# MED_ESP32_C3_0002.net
KiCad netlist of a schematic drawn in EAGLE
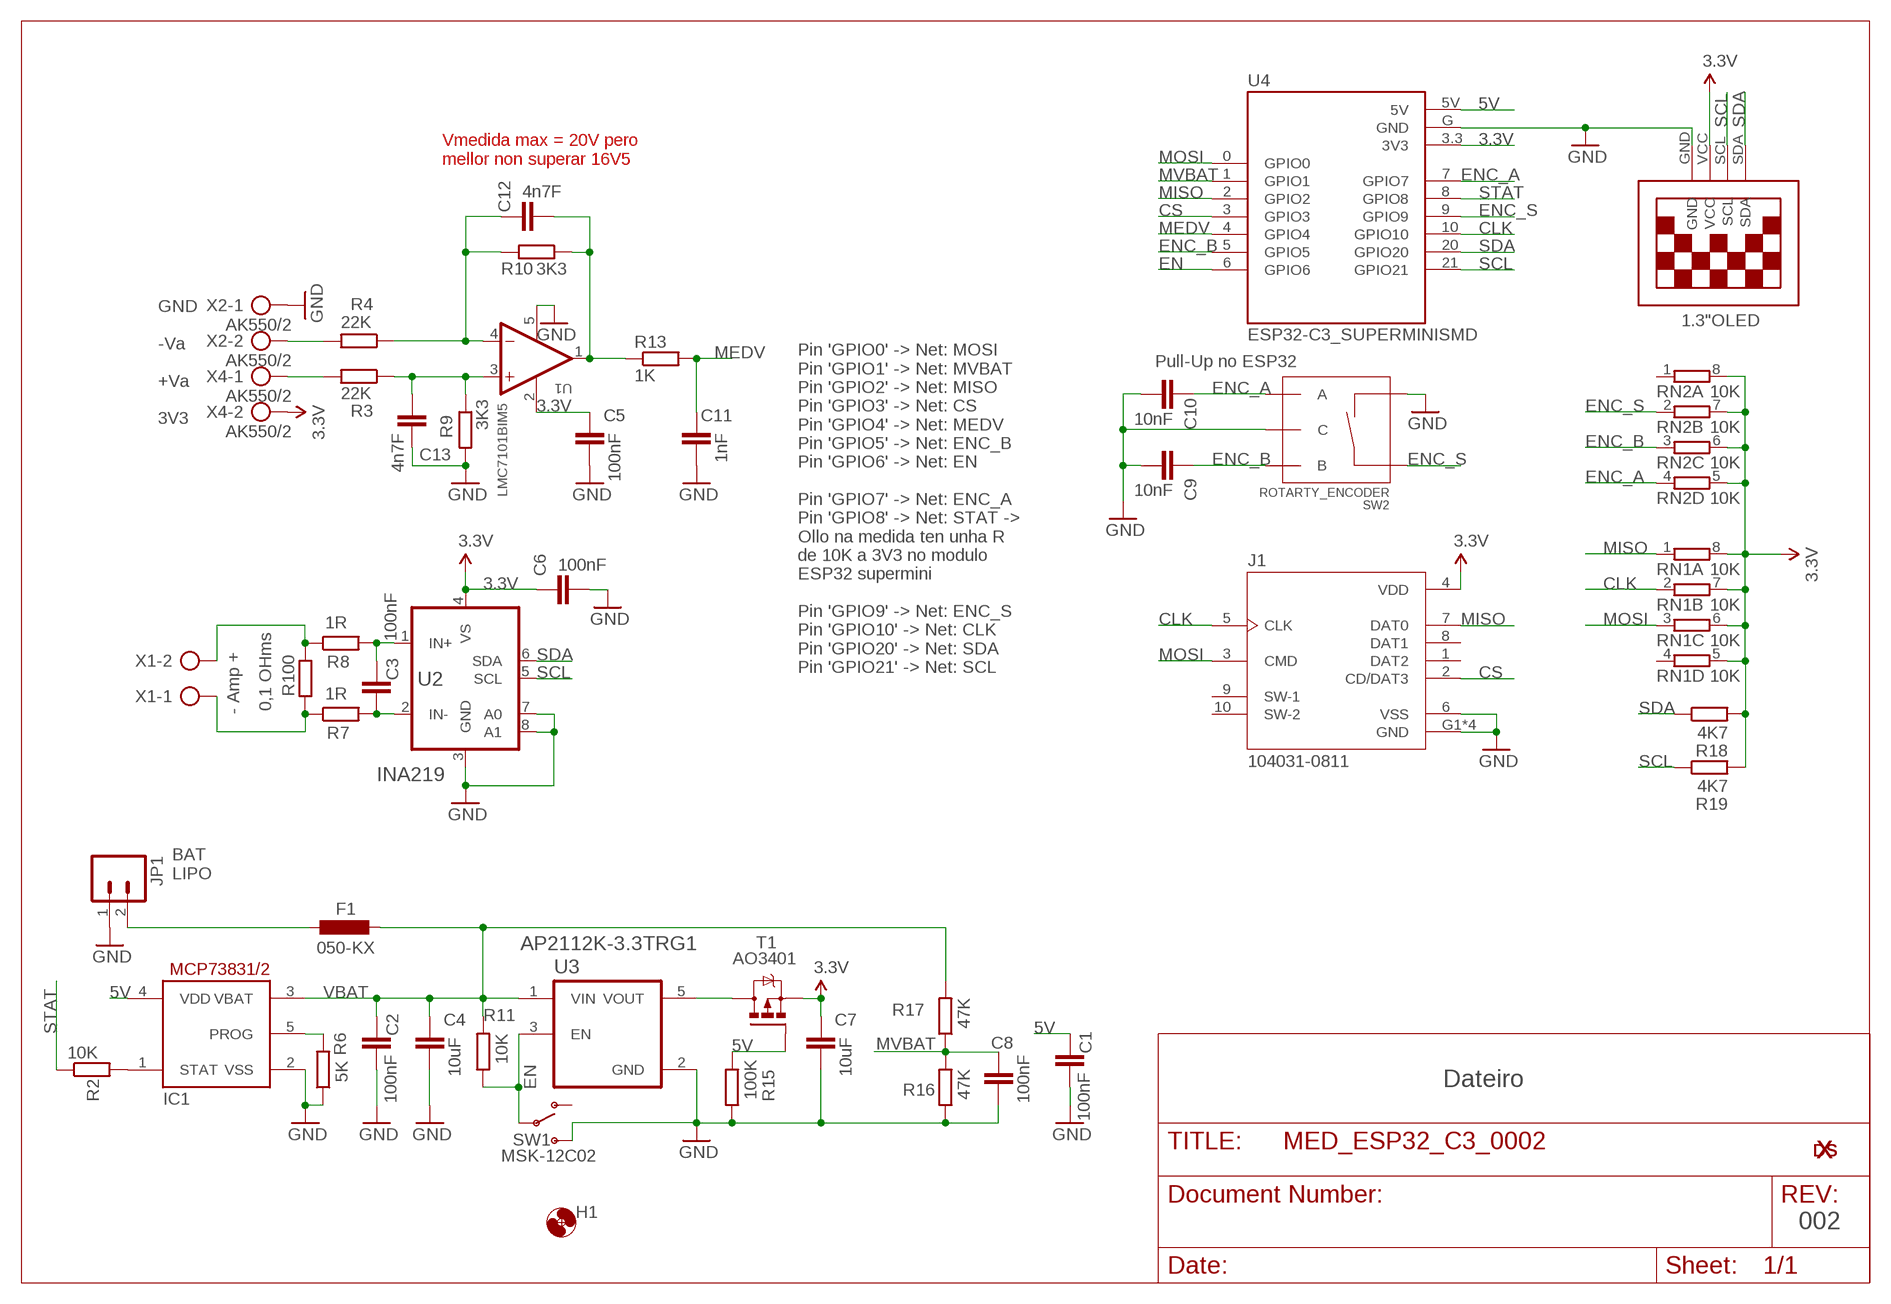
[diagram p0: schematic, sheet 1]

(export (version "E")
  (design (tool "Eeschema 10.0.6"))
  (components
    (comp (ref "C1")
      (value "100nF")
      (footprint "eagle-import:C0603")
      (libsource (lib "eagle-import") (part "C-EUC0603"))
    )
    (comp (ref "C2")
      (value "100nF")
      (footprint "eagle-import:C0603")
      (libsource (lib "eagle-import") (part "C-EUC0603"))
    )
    (comp (ref "C3")
      (value "100nF")
      (footprint "eagle-import:C0603")
      (libsource (lib "eagle-import") (part "C-EUC0603"))
    )
    (comp (ref "C4")
      (value "10uF")
      (footprint "eagle-import:C1206")
      (libsource (lib "eagle-import") (part "C-EUC1206"))
    )
    (comp (ref "C5")
      (value "100nF")
      (footprint "eagle-import:C0603")
      (libsource (lib "eagle-import") (part "C-EUC0603"))
    )
    (comp (ref "C6")
      (value "100nF")
      (footprint "eagle-import:C0603")
      (libsource (lib "eagle-import") (part "C-EUC0603"))
    )
    (comp (ref "C7")
      (value "10uF")
      (footprint "eagle-import:C1206")
      (libsource (lib "eagle-import") (part "C-EUC1206"))
    )
    (comp (ref "C8")
      (value "100nF")
      (footprint "eagle-import:C0603")
      (libsource (lib "eagle-import") (part "C-EUC0603"))
    )
    (comp (ref "C9")
      (value "10nF")
      (footprint "eagle-import:C0603")
      (libsource (lib "eagle-import") (part "C-EUC0603"))
    )
    (comp (ref "C10")
      (value "10nF")
      (footprint "eagle-import:C0603")
      (libsource (lib "eagle-import") (part "C-EUC0603"))
    )
    (comp (ref "C11")
      (value "1nF")
      (footprint "eagle-import:C0603")
      (libsource (lib "eagle-import") (part "C-EUC0603"))
    )
    (comp (ref "C12")
      (value "4n7F")
      (footprint "eagle-import:C0603")
      (libsource (lib "eagle-import") (part "C-EUC0603"))
    )
    (comp (ref "C13")
      (value "4n7F")
      (footprint "eagle-import:C0603")
      (libsource (lib "eagle-import") (part "C-EUC0603"))
    )
    (comp (ref "F1")
      (value "050-KX")
      (footprint "eagle-import:L3225M")
      (libsource (lib "eagle-import") (part "L-EUL3225M"))
    )
    (comp (ref "H1")
      (value "HOLES_MOUNT-HOLE3.2")
      (footprint "eagle-import:HOLES_3,2")
      (libsource (lib "eagle-import") (part "HOLES_MOUNT-HOLE3.2"))
    )
    (comp (ref "IC1")
      (value "MCP73831T-2")
      (footprint "eagle-import:SOT23-5L")
      (libsource (lib "eagle-import") (part "MCP73831/OT"))
    )
    (comp (ref "J1")
      (value "104031-0811")
      (footprint "eagle-import:MOLEX_104031-0811")
      (fields (field (name "MF") "Molex"))
      (libsource (lib "eagle-import") (part "104031-0811"))
    )
    (comp (ref "JP1")
      (value "M02JST-PTH-VERT")
      (footprint "eagle-import:JST-2-PTH-VERT")
      (libsource (lib "eagle-import") (part "M02JST-PTH-VERT"))
    )
    (comp (ref "R2")
      (value "10K")
      (footprint "eagle-import:R0603")
      (libsource (lib "eagle-import") (part "R-EU_R0603"))
    )
    (comp (ref "R3")
      (value "22K")
      (footprint "eagle-import:R0603")
      (libsource (lib "eagle-import") (part "R-EU_R0603"))
    )
    (comp (ref "R4")
      (value "22K")
      (footprint "eagle-import:R0603")
      (libsource (lib "eagle-import") (part "R-EU_R0603"))
    )
    (comp (ref "R5")
      (value "R100")
      (footprint "eagle-import:R1210")
      (libsource (lib "eagle-import") (part "R-EU_R1210"))
    )
    (comp (ref "R6")
      (value "5K")
      (footprint "eagle-import:R0603")
      (libsource (lib "eagle-import") (part "R-EU_R0603"))
    )
    (comp (ref "R7")
      (value "1R")
      (footprint "eagle-import:R0603")
      (libsource (lib "eagle-import") (part "R-EU_R0603"))
    )
    (comp (ref "R8")
      (value "1R")
      (footprint "eagle-import:R0603")
      (libsource (lib "eagle-import") (part "R-EU_R0603"))
    )
    (comp (ref "R9")
      (value "3K3")
      (footprint "eagle-import:R0603")
      (libsource (lib "eagle-import") (part "R-EU_R0603"))
    )
    (comp (ref "R10")
      (value "3K3")
      (footprint "eagle-import:R0603")
      (libsource (lib "eagle-import") (part "R-EU_R0603"))
    )
    (comp (ref "R11")
      (value "10K")
      (footprint "eagle-import:R0603")
      (libsource (lib "eagle-import") (part "R-EU_R0603"))
    )
    (comp (ref "R13")
      (value "1K")
      (footprint "eagle-import:R0603")
      (libsource (lib "eagle-import") (part "R-EU_R0603"))
    )
    (comp (ref "R15")
      (value "100K")
      (footprint "eagle-import:R0603")
      (libsource (lib "eagle-import") (part "R-EU_R0603"))
    )
    (comp (ref "R16")
      (value "47K")
      (footprint "eagle-import:R0603")
      (libsource (lib "eagle-import") (part "R-EU_R0603"))
    )
    (comp (ref "R17")
      (value "47K")
      (footprint "eagle-import:R0603")
      (libsource (lib "eagle-import") (part "R-EU_R0603"))
    )
    (comp (ref "R18")
      (value "4K7")
      (footprint "eagle-import:R0603")
      (libsource (lib "eagle-import") (part "R-EU_R0603"))
    )
    (comp (ref "R19")
      (value "4K7")
      (footprint "eagle-import:R0603")
      (libsource (lib "eagle-import") (part "R-EU_R0603"))
    )
    (comp (ref "RN1")
      (value "10K")
      (footprint "eagle-import:RESISTOR-DIL_0603-ARC")
      (libsource (lib "eagle-import") (part "RESISTOR-DIL_4R-N0603-ARC"))
    )
    (comp (ref "RN2")
      (value "10K")
      (footprint "eagle-import:RESISTOR-DIL_0603-ARV")
      (libsource (lib "eagle-import") (part "RESISTOR-DIL_4R-N0603-ARV"))
    )
    (comp (ref "SW1")
      (value "MSK-12C02")
      (footprint "eagle-import:KPS-1290")
      (libsource (lib "eagle-import") (part "SWITCH_SPDT"))
    )
    (comp (ref "SW2")
      (value "ROTARTY_ENCODER")
      (footprint "eagle-import:ROTARY_ENC_PLAIN")
      (libsource (lib "eagle-import") (part "ROTARTY_ENCODER"))
    )
    (comp (ref "T1")
      (value "AO3401")
      (footprint "eagle-import:SOT23")
      (libsource (lib "eagle-import") (part "MOSFET-PCHANNEL"))
    )
    (comp (ref "U$1")
      (value "13\"OLED13\"OLED")
      (footprint "eagle-import:1.3_OLED")
      (libsource (lib "eagle-import") (part "13{dblquote}OLED13{dblquote}OLED"))
    )
    (comp (ref "U$2")
      (value "XDESIG5MM")
      (footprint "eagle-import:XDESIG_CU")
      (libsource (lib "eagle-import") (part "XDESIG5MM"))
    )
    (comp (ref "U$3")
      (value "XDESIG21")
      (footprint "eagle-import:XDESIG")
      (libsource (lib "eagle-import") (part "XDESIG21"))
    )
    (comp (ref "U$4")
      (value "XDESIG21")
      (footprint "eagle-import:XDESIG")
      (libsource (lib "eagle-import") (part "XDESIG21"))
    )
    (comp (ref "U$5")
      (value "XDESIG5MM")
      (footprint "eagle-import:XDESIG_CU")
      (libsource (lib "eagle-import") (part "XDESIG5MM"))
    )
    (comp (ref "U1")
      (value "LMC7101BIM5")
      (footprint "eagle-import:SOT95P280X145-5N")
      (fields (field (name "MF") "Texas Instruments") (field (name "MP") "LMC7101BIM5/NOPB"))
      (libsource (lib "eagle-import") (part "LMC7101BIM5"))
    )
    (comp (ref "U2")
      (value "INA219")
      (footprint "eagle-import:SOT65P280X145-8N")
      (fields (field (name "MF") "Texas Instruments") (field (name "MP") "INA219AIDCNRG4"))
      (libsource (lib "eagle-import") (part "INA219"))
    )
    (comp (ref "U3")
      (value "AP2112K-3.3TRG1")
      (footprint "eagle-import:SOT95P285X140-5N")
      (fields (field (name "MF") "Diodes Inc."))
      (libsource (lib "eagle-import") (part "AP2112K-3.3TRG1"))
    )
    (comp (ref "U4")
      (value "ESP32-C3_SUPERMINISMD")
      (footprint "eagle-import:MODULE_ESP-C3_SUPERMINI_SMD")
      (libsource (lib "eagle-import") (part "ESP32-C3_SUPERMINISMD"))
    )
    (comp (ref "X1")
      (value "AK500/2")
      (footprint "eagle-import:AK500_2")
      (libsource (lib "eagle-import") (part "AK500/2"))
    )
    (comp (ref "X2")
      (value "AK550/2")
      (footprint "eagle-import:AK550_2")
      (libsource (lib "eagle-import") (part "AK550/2"))
    )
    (comp (ref "X4")
      (value "AK550/2")
      (footprint "eagle-import:AK550_2")
      (libsource (lib "eagle-import") (part "AK550/2"))
    )
  )
  (nets
    (net (code "1") (name "/5V") (class "Default")
      (node (ref "C1") (pin "1") (pinfunction "1_1") (pintype "passive"))
      (node (ref "IC1") (pin "4") (pinfunction "VDD_4") (pintype "power_in"))
      (node (ref "R15") (pin "2") (pinfunction "2_2") (pintype "passive"))
      (node (ref "T1") (pin "1") (pinfunction "G_1") (pintype "passive"))
      (node (ref "U4") (pin "5V") (pinfunction "5V_5V") (pintype "power_in"))
    )
    (net (code "2") (name "/CLK") (class "Default")
      (node (ref "J1") (pin "5") (pinfunction "CLK_5") (pintype "input"))
      (node (ref "RN1") (pin "2") (pinfunction "1_2") (pintype "passive"))
      (node (ref "U4") (pin "10") (pinfunction "GPIO10_10") (pintype "bidirectional"))
    )
    (net (code "3") (name "/CS") (class "Default")
      (node (ref "J1") (pin "2") (pinfunction "CD/DAT3_2") (pintype "bidirectional"))
      (node (ref "U4") (pin "3") (pinfunction "GPIO3_3") (pintype "bidirectional"))
    )
    (net (code "4") (name "/EN") (class "Default")
      (node (ref "R11") (pin "1") (pinfunction "1_1") (pintype "passive"))
      (node (ref "SW1") (pin "P") (pinfunction "P_P") (pintype "passive"))
      (node (ref "U3") (pin "3") (pinfunction "EN_3") (pintype "input"))
      (node (ref "U4") (pin "6") (pinfunction "GPIO6_6") (pintype "bidirectional"))
    )
    (net (code "5") (name "/ENC_A") (class "Default")
      (node (ref "C10") (pin "2") (pinfunction "2_2") (pintype "passive"))
      (node (ref "RN2") (pin "4") (pinfunction "1_4") (pintype "passive"))
      (node (ref "SW2") (pin "A") (pinfunction "A_A") (pintype "bidirectional"))
      (node (ref "U4") (pin "7") (pinfunction "GPIO7_7") (pintype "bidirectional"))
    )
    (net (code "6") (name "/ENC_B") (class "Default")
      (node (ref "C9") (pin "2") (pinfunction "2_2") (pintype "passive"))
      (node (ref "RN2") (pin "3") (pinfunction "1_3") (pintype "passive"))
      (node (ref "SW2") (pin "B") (pinfunction "B_B") (pintype "bidirectional"))
      (node (ref "U4") (pin "5") (pinfunction "GPIO5_5") (pintype "bidirectional"))
    )
    (net (code "7") (name "/ENC_S") (class "Default")
      (node (ref "RN2") (pin "2") (pinfunction "1_2") (pintype "passive"))
      (node (ref "SW2") (pin "SW+") (pinfunction "SW+_SW+") (pintype "bidirectional"))
      (node (ref "U4") (pin "9") (pinfunction "GPIO9_9") (pintype "bidirectional"))
    )
    (net (code "8") (name "/MEDV") (class "Default")
      (node (ref "C11") (pin "2") (pinfunction "2_2") (pintype "passive"))
      (node (ref "R13") (pin "2") (pinfunction "2_2") (pintype "passive"))
      (node (ref "U4") (pin "4") (pinfunction "GPIO4_4") (pintype "bidirectional"))
    )
    (net (code "9") (name "/MISO") (class "Default")
      (node (ref "J1") (pin "7") (pinfunction "DAT0_7") (pintype "bidirectional"))
      (node (ref "RN1") (pin "1") (pinfunction "1_1") (pintype "passive"))
      (node (ref "U4") (pin "2") (pinfunction "GPIO2_2") (pintype "bidirectional"))
    )
    (net (code "10") (name "/MOSI") (class "Default")
      (node (ref "J1") (pin "3") (pinfunction "CMD_3") (pintype "bidirectional"))
      (node (ref "RN1") (pin "3") (pinfunction "1_3") (pintype "passive"))
      (node (ref "U4") (pin "0") (pinfunction "GPIO0_0") (pintype "bidirectional"))
    )
    (net (code "11") (name "/MVBAT") (class "Default")
      (node (ref "C8") (pin "1") (pinfunction "1_1") (pintype "passive"))
      (node (ref "R16") (pin "2") (pinfunction "2_2") (pintype "passive"))
      (node (ref "R17") (pin "1") (pinfunction "1_1") (pintype "passive"))
      (node (ref "U4") (pin "1") (pinfunction "GPIO1_1") (pintype "bidirectional"))
    )
    (net (code "12") (name "/SCL") (class "Default")
      (node (ref "R19") (pin "1") (pinfunction "1_1") (pintype "passive"))
      (node (ref "U$1") (pin "SCL") (pinfunction "SCL_SCL") (pintype "bidirectional"))
      (node (ref "U2") (pin "5") (pinfunction "SCL_5") (pintype "input"))
      (node (ref "U4") (pin "21") (pinfunction "GPIO21_21") (pintype "bidirectional"))
    )
    (net (code "13") (name "/SDA") (class "Default")
      (node (ref "R18") (pin "1") (pinfunction "1_1") (pintype "passive"))
      (node (ref "U$1") (pin "SDA") (pinfunction "SDA_SDA") (pintype "bidirectional"))
      (node (ref "U2") (pin "6") (pinfunction "SDA_6") (pintype "bidirectional"))
      (node (ref "U4") (pin "20") (pinfunction "GPIO20_20") (pintype "bidirectional"))
    )
    (net (code "14") (name "/STAT") (class "Default")
      (node (ref "R2") (pin "1") (pinfunction "1_1") (pintype "passive"))
      (node (ref "U4") (pin "8") (pinfunction "GPIO8_8") (pintype "bidirectional"))
    )
    (net (code "15") (name "/VBAT") (class "Default")
      (node (ref "C2") (pin "1") (pinfunction "1_1") (pintype "passive"))
      (node (ref "C4") (pin "2") (pinfunction "2_2") (pintype "passive"))
      (node (ref "F1") (pin "1") (pinfunction "1_1") (pintype "passive"))
      (node (ref "IC1") (pin "3") (pinfunction "VBAT_3") (pintype "bidirectional"))
      (node (ref "R11") (pin "2") (pinfunction "2_2") (pintype "passive"))
      (node (ref "R17") (pin "2") (pinfunction "2_2") (pintype "passive"))
      (node (ref "U3") (pin "1") (pinfunction "VIN_1") (pintype "power_in"))
    )
    (net (code "16") (name "3.3V") (class "Default")
      (node (ref "C5") (pin "2") (pinfunction "2_2") (pintype "passive"))
      (node (ref "C6") (pin "2") (pinfunction "2_2") (pintype "passive"))
      (node (ref "C7") (pin "2") (pinfunction "2_2") (pintype "passive"))
      (node (ref "J1") (pin "4") (pinfunction "VDD_4") (pintype "power_in"))
      (node (ref "R18") (pin "2") (pinfunction "2_2") (pintype "passive"))
      (node (ref "R19") (pin "2") (pinfunction "2_2") (pintype "passive"))
      (node (ref "RN1") (pin "5") (pinfunction "2_5") (pintype "passive"))
      (node (ref "RN1") (pin "6") (pinfunction "2_6") (pintype "passive"))
      (node (ref "RN1") (pin "7") (pinfunction "2_7") (pintype "passive"))
      (node (ref "RN1") (pin "8") (pinfunction "2_8") (pintype "passive"))
      (node (ref "RN2") (pin "5") (pinfunction "2_5") (pintype "passive"))
      (node (ref "RN2") (pin "6") (pinfunction "2_6") (pintype "passive"))
      (node (ref "RN2") (pin "7") (pinfunction "2_7") (pintype "passive"))
      (node (ref "RN2") (pin "8") (pinfunction "2_8") (pintype "passive"))
      (node (ref "T1") (pin "2") (pinfunction "S_2") (pintype "passive"))
      (node (ref "U$1") (pin "VCC") (pinfunction "VCC_VCC") (pintype "bidirectional"))
      (node (ref "U1") (pin "2") (pinfunction "V+_2") (pintype "power_in"))
      (node (ref "U2") (pin "4") (pinfunction "VS_4") (pintype "power_in"))
      (node (ref "U4") (pin "3.3") (pinfunction "3V3_3.3") (pintype "power_in"))
      (node (ref "X4") (pin "2") (pinfunction "KL_2") (pintype "passive"))
    )
    (net (code "17") (name "GND") (class "Default")
      (node (ref "C1") (pin "2") (pinfunction "2_2") (pintype "passive"))
      (node (ref "C10") (pin "1") (pinfunction "1_1") (pintype "passive"))
      (node (ref "C11") (pin "1") (pinfunction "1_1") (pintype "passive"))
      (node (ref "C13") (pin "2") (pinfunction "2_2") (pintype "passive"))
      (node (ref "C2") (pin "2") (pinfunction "2_2") (pintype "passive"))
      (node (ref "C4") (pin "1") (pinfunction "1_1") (pintype "passive"))
      (node (ref "C5") (pin "1") (pinfunction "1_1") (pintype "passive"))
      (node (ref "C6") (pin "1") (pinfunction "1_1") (pintype "passive"))
      (node (ref "C7") (pin "1") (pinfunction "1_1") (pintype "passive"))
      (node (ref "C8") (pin "2") (pinfunction "2_2") (pintype "passive"))
      (node (ref "C9") (pin "1") (pinfunction "1_1") (pintype "passive"))
      (node (ref "IC1") (pin "2") (pinfunction "VSS_2") (pintype "power_in"))
      (node (ref "J1") (pin "6") (pinfunction "VSS_6") (pintype "power_in"))
      (node (ref "J1") (pin "G1") (pinfunction "GND_G1") (pintype "power_in"))
      (node (ref "J1") (pin "G2") (pinfunction "GND_G2") (pintype "power_in"))
      (node (ref "J1") (pin "G3") (pinfunction "GND_G3") (pintype "power_in"))
      (node (ref "J1") (pin "G4") (pinfunction "GND_G4") (pintype "power_in"))
      (node (ref "JP1") (pin "1") (pinfunction "1_1") (pintype "passive"))
      (node (ref "R15") (pin "1") (pinfunction "1_1") (pintype "passive"))
      (node (ref "R16") (pin "1") (pinfunction "1_1") (pintype "passive"))
      (node (ref "R6") (pin "1") (pinfunction "1_1") (pintype "passive"))
      (node (ref "R9") (pin "2") (pinfunction "2_2") (pintype "passive"))
      (node (ref "SW1") (pin "S") (pinfunction "S_S") (pintype "passive"))
      (node (ref "SW2") (pin "C") (pinfunction "C_C") (pintype "bidirectional"))
      (node (ref "SW2") (pin "SW-") (pinfunction "SW-_SW-") (pintype "bidirectional"))
      (node (ref "U$1") (pin "GND") (pinfunction "GND_GND") (pintype "bidirectional"))
      (node (ref "U1") (pin "5") (pinfunction "V-_5") (pintype "power_in"))
      (node (ref "U2") (pin "3") (pinfunction "GND_3") (pintype "power_in"))
      (node (ref "U2") (pin "7") (pinfunction "A0_7") (pintype "input"))
      (node (ref "U2") (pin "8") (pinfunction "A1_8") (pintype "input"))
      (node (ref "U3") (pin "2") (pinfunction "GND_2") (pintype "power_in"))
      (node (ref "U4") (pin "G") (pinfunction "GND_G") (pintype "power_in"))
      (node (ref "X2") (pin "1") (pinfunction "KL_1") (pintype "passive"))
    )
    (net (code "18") (name "Net-(F1-Pad2)") (class "Default")
      (node (ref "F1") (pin "2") (pinfunction "2_2") (pintype "passive"))
      (node (ref "JP1") (pin "2") (pinfunction "2_2") (pintype "passive"))
    )
    (net (code "19") (name "Net-(IC1-PROG)") (class "Default")
      (node (ref "IC1") (pin "5") (pinfunction "PROG_5") (pintype "input"))
      (node (ref "R6") (pin "2") (pinfunction "2_2") (pintype "passive"))
    )
    (net (code "20") (name "Net-(IC1-STAT)") (class "Default")
      (node (ref "IC1") (pin "1") (pinfunction "STAT_1") (pintype "output"))
      (node (ref "R2") (pin "2") (pinfunction "2_2") (pintype "passive"))
    )
    (net (code "21") (name "Net-(T1-D)") (class "Default")
      (node (ref "T1") (pin "3") (pinfunction "D_3") (pintype "passive"))
      (node (ref "U3") (pin "5") (pinfunction "VOUT_5") (pintype "power_in"))
    )
    (net (code "22") (name "Net-(U1-+IN)") (class "Default")
      (node (ref "C13") (pin "1") (pinfunction "1_1") (pintype "passive"))
      (node (ref "R3") (pin "1") (pinfunction "1_1") (pintype "passive"))
      (node (ref "R9") (pin "1") (pinfunction "1_1") (pintype "passive"))
      (node (ref "U1") (pin "3") (pinfunction "+IN_3") (pintype "input"))
    )
    (net (code "23") (name "Net-(U1--IN)") (class "Default")
      (node (ref "C12") (pin "2") (pinfunction "2_2") (pintype "passive"))
      (node (ref "R10") (pin "2") (pinfunction "2_2") (pintype "passive"))
      (node (ref "R4") (pin "1") (pinfunction "1_1") (pintype "passive"))
      (node (ref "U1") (pin "4") (pinfunction "-IN_4") (pintype "input"))
    )
    (net (code "24") (name "Net-(U1-OUT)") (class "Default")
      (node (ref "C12") (pin "1") (pinfunction "1_1") (pintype "passive"))
      (node (ref "R10") (pin "1") (pinfunction "1_1") (pintype "passive"))
      (node (ref "R13") (pin "1") (pinfunction "1_1") (pintype "passive"))
      (node (ref "U1") (pin "1") (pinfunction "OUT_1") (pintype "output"))
    )
    (net (code "25") (name "Net-(U2-IN+)") (class "Default")
      (node (ref "C3") (pin "1") (pinfunction "1_1") (pintype "passive"))
      (node (ref "R8") (pin "2") (pinfunction "2_2") (pintype "passive"))
      (node (ref "U2") (pin "1") (pinfunction "IN+_1") (pintype "input"))
    )
    (net (code "26") (name "Net-(U2-IN-)") (class "Default")
      (node (ref "C3") (pin "2") (pinfunction "2_2") (pintype "passive"))
      (node (ref "R7") (pin "2") (pinfunction "2_2") (pintype "passive"))
      (node (ref "U2") (pin "2") (pinfunction "IN-_2") (pintype "input"))
    )
    (net (code "27") (name "Net-(X1A-KL)") (class "Default")
      (node (ref "R5") (pin "1") (pinfunction "1_1") (pintype "passive"))
      (node (ref "R7") (pin "1") (pinfunction "1_1") (pintype "passive"))
      (node (ref "X1") (pin "1") (pinfunction "KL_1") (pintype "passive"))
    )
    (net (code "28") (name "Net-(X1B-KL)") (class "Default")
      (node (ref "R5") (pin "2") (pinfunction "2_2") (pintype "passive"))
      (node (ref "R8") (pin "1") (pinfunction "1_1") (pintype "passive"))
      (node (ref "X1") (pin "2") (pinfunction "KL_2") (pintype "passive"))
    )
    (net (code "29") (name "Net-(X2B-KL)") (class "Default")
      (node (ref "R4") (pin "2") (pinfunction "2_2") (pintype "passive"))
      (node (ref "X2") (pin "2") (pinfunction "KL_2") (pintype "passive"))
    )
    (net (code "30") (name "Net-(X4A-KL)") (class "Default")
      (node (ref "R3") (pin "2") (pinfunction "2_2") (pintype "passive"))
      (node (ref "X4") (pin "1") (pinfunction "KL_1") (pintype "passive"))
    )
    (net (code "31") (name "unconnected-(J1-DAT1-Pad8)") (class "Default")
      (node (ref "J1") (pin "8") (pinfunction "DAT1_8") (pintype "bidirectional"))
    )
    (net (code "32") (name "unconnected-(J1-DAT2-Pad1)") (class "Default")
      (node (ref "J1") (pin "1") (pinfunction "DAT2_1") (pintype "bidirectional"))
    )
    (net (code "33") (name "unconnected-(J1-SW-1-Pad9)") (class "Default")
      (node (ref "J1") (pin "9") (pinfunction "SW-1_9") (pintype "passive"))
    )
    (net (code "34") (name "unconnected-(J1-SW-2-Pad10)") (class "Default")
      (node (ref "J1") (pin "10") (pinfunction "SW-2_10") (pintype "passive"))
    )
    (net (code "35") (name "unconnected-(RN1D-1-Pad4)") (class "Default")
      (node (ref "RN1") (pin "4") (pinfunction "1_4") (pintype "passive"))
    )
    (net (code "36") (name "unconnected-(RN2-Pad1)") (class "Default")
      (node (ref "RN2") (pin "1") (pinfunction "1_1") (pintype "passive"))
    )
    (net (code "37") (name "unconnected-(SW1-PadO)") (class "Default")
      (node (ref "SW1") (pin "O") (pinfunction "O_O") (pintype "passive"))
    )
  )
)
